# WL_430.net
KiCad netlist of a schematic drawn in Altium Designer
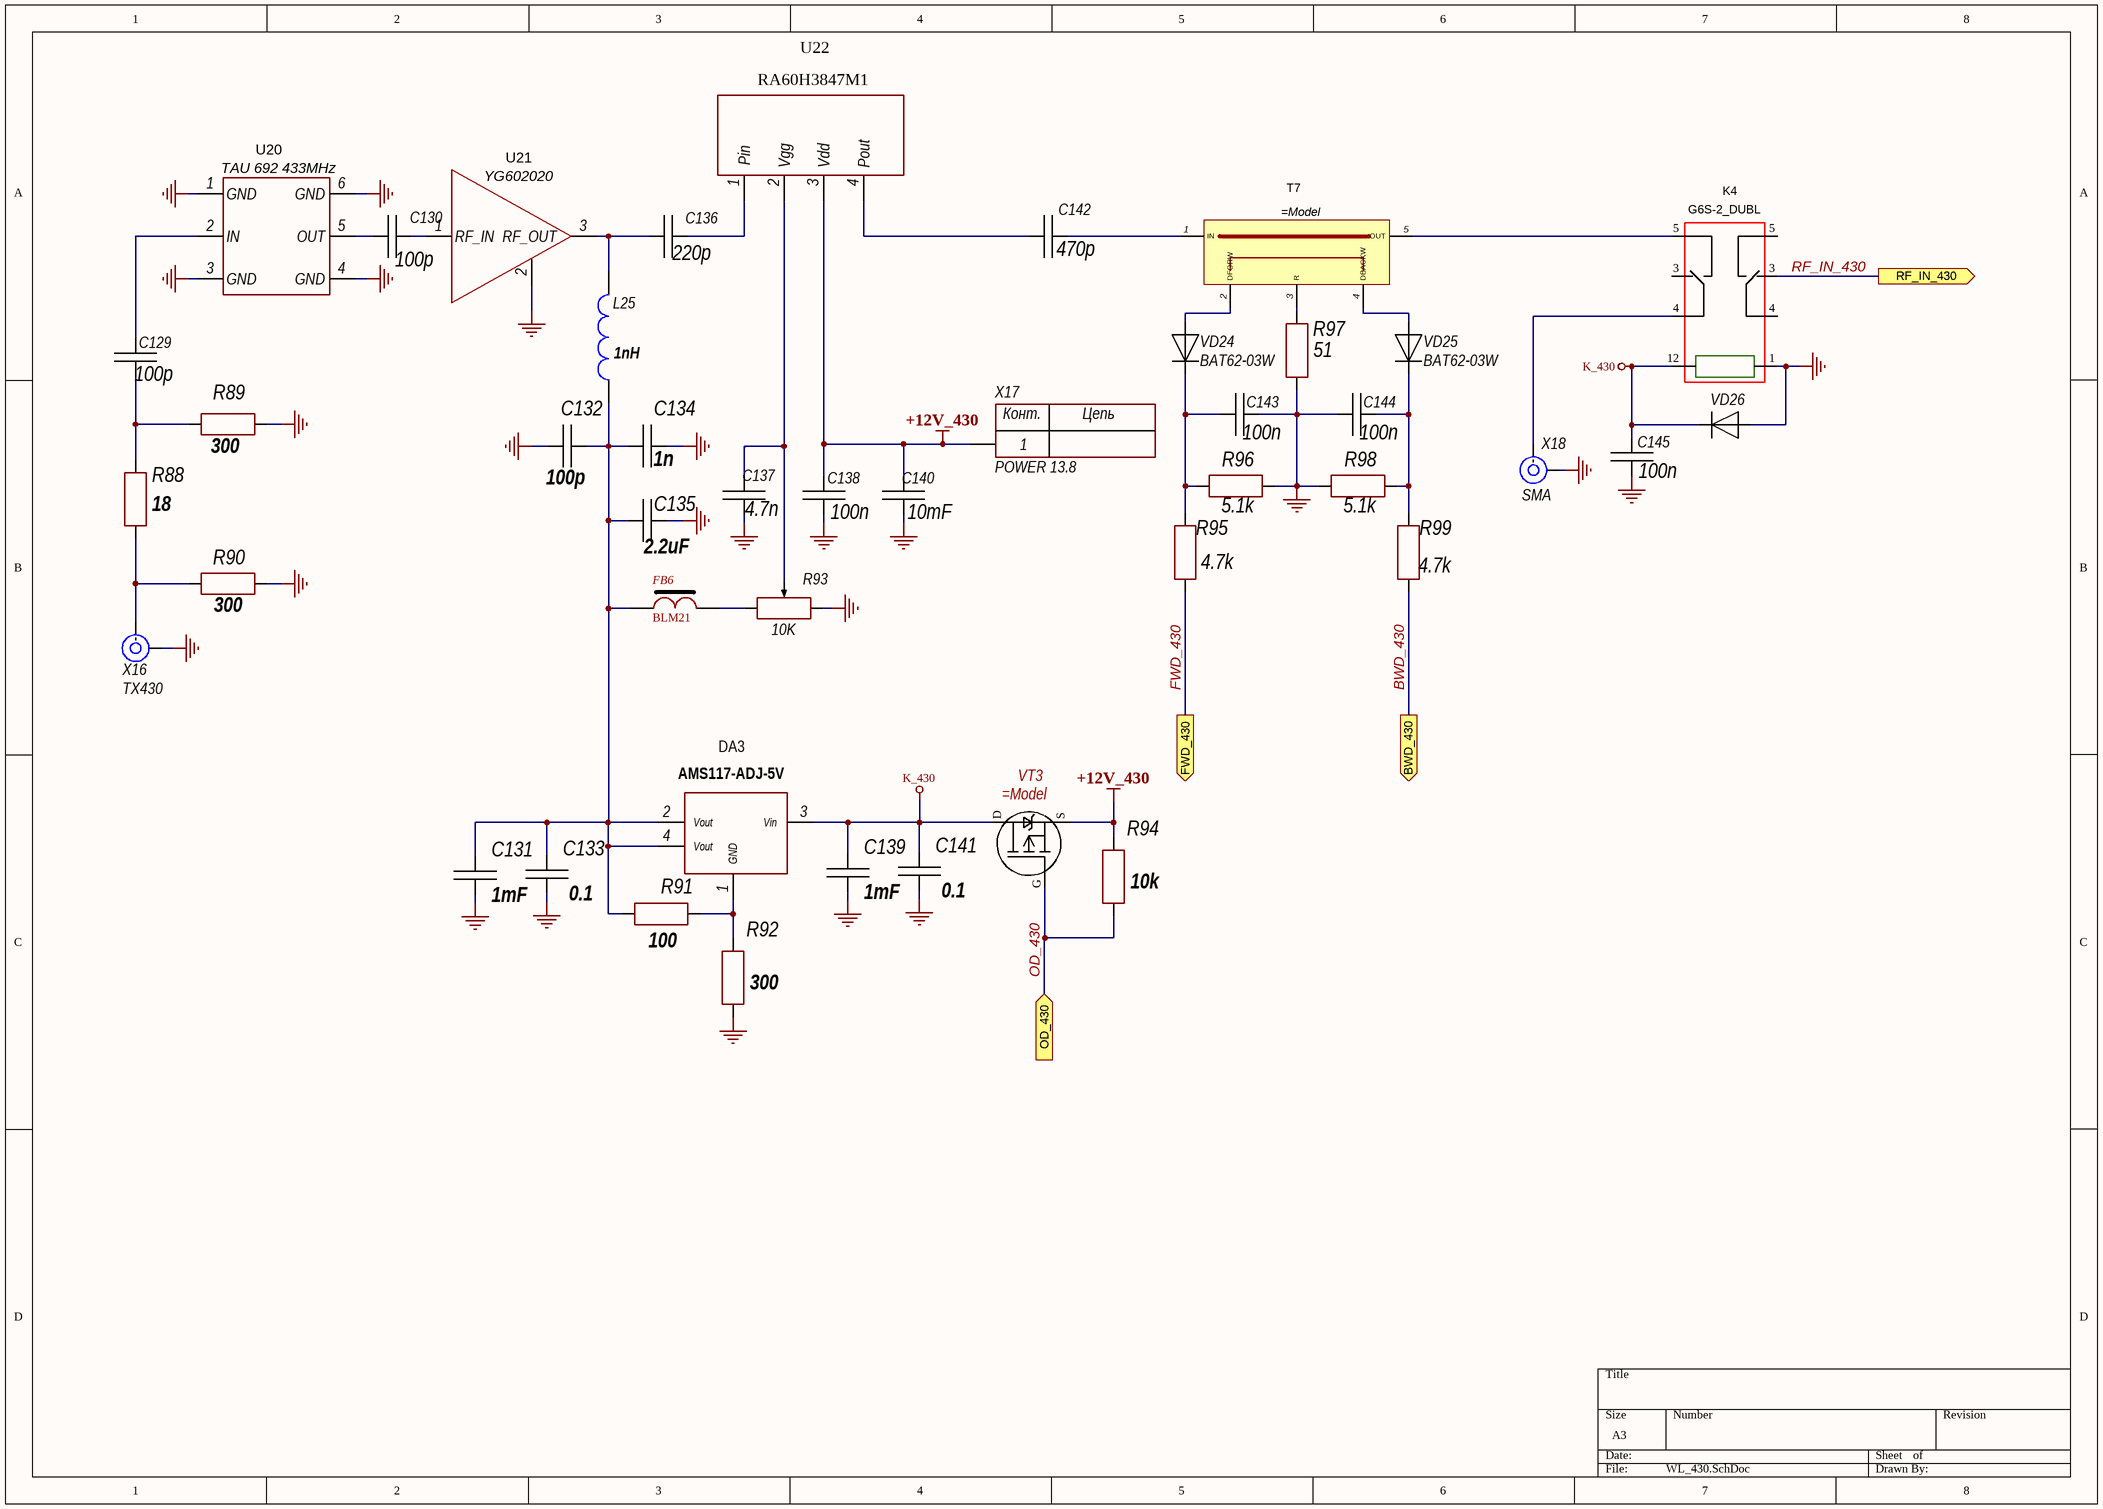
[diagram p0: WL_430.SchDoc]

(export (version "E")
  (design (tool "Eeschema 10.0.6"))
  (components
    (comp (ref "C129")
      (value "100p")
      (footprint "standard:CH0805C")
      (libsource (lib "Discrete") (part "Capacitor"))
    )
    (comp (ref "C130")
      (value "100p")
      (footprint "standard:CH0805C")
      (libsource (lib "Discrete") (part "Capacitor"))
    )
    (comp (ref "C131")
      (value "1mF")
      (footprint "standard:CH0805C")
      (libsource (lib "Discrete") (part "Capacitor"))
    )
    (comp (ref "C132")
      (value "100p")
      (footprint "standard:CH0805C")
      (libsource (lib "Discrete") (part "Capacitor"))
    )
    (comp (ref "C133")
      (value "0.1")
      (footprint "standard:CH0805C")
      (libsource (lib "Discrete") (part "Capacitor"))
    )
    (comp (ref "C134")
      (value "1n")
      (footprint "standard:CH0805C")
      (libsource (lib "Discrete") (part "Capacitor"))
    )
    (comp (ref "C135")
      (value "2.2uF")
      (footprint "standard:CH0805C")
      (libsource (lib "Discrete") (part "Capacitor"))
    )
    (comp (ref "C136")
      (value "220p")
      (footprint "standard:CH0805C")
      (libsource (lib "Discrete") (part "Capacitor"))
    )
    (comp (ref "C137")
      (value "4.7n")
      (footprint "standard:CH0805C")
      (libsource (lib "Discrete") (part "Capacitor"))
    )
    (comp (ref "C138")
      (value "100n")
      (footprint "standard:CH1206C")
      (libsource (lib "Discrete") (part "Capacitor"))
    )
    (comp (ref "C139")
      (value "1mF")
      (footprint "standard:CH0805C")
      (libsource (lib "Discrete") (part "Capacitor"))
    )
    (comp (ref "C140")
      (value "10mF")
      (footprint "standard:CH1206C")
      (libsource (lib "Discrete") (part "Capacitor"))
    )
    (comp (ref "C141")
      (value "0.1")
      (footprint "standard:CH0805C")
      (libsource (lib "Discrete") (part "Capacitor"))
    )
    (comp (ref "C142")
      (value "470p")
      (footprint "standard:CH1210C")
      (libsource (lib "Discrete") (part "Capacitor"))
    )
    (comp (ref "C143")
      (value "100n")
      (footprint "standard:CH0805C")
      (libsource (lib "Discrete") (part "Capacitor"))
    )
    (comp (ref "C144")
      (value "100n")
      (footprint "standard:CH0805C")
      (libsource (lib "Discrete") (part "Capacitor"))
    )
    (comp (ref "C145")
      (value "100n")
      (footprint "standard:CH0805C")
      (libsource (lib "") (part "Capacitor_1"))
    )
    (comp (ref "DA3") (value "AMS117-ADJ-5V") (footprint "SOT223") (libsource (lib "Analog") (part "AMS117")))
    (comp (ref "FB6") (value "BLM21") (footprint "CH0805L") (libsource (lib "Discrete") (part "FB-1")))
    (comp (ref "K4")
      (value "G6S-2_DUBL")
      (footprint "G6S-2_DUBL")
      (libsource (lib "Relay") (part "G6S-2_DUBL"))
    )
    (comp (ref "L25")
      (value "1nH")
      (footprint "katuhka")
      (libsource (lib "Transformers") (part "Inductor ring"))
    )
    (comp (ref "R88") (value "18") (footprint "standard:CH0805R") (libsource (lib "") (part "Resistor_1")))
    (comp (ref "R89") (value "300") (footprint "standard:CH0805R") (libsource (lib "") (part "Resistor_2")))
    (comp (ref "R90") (value "300") (footprint "standard:CH0805R") (libsource (lib "") (part "Resistor_2")))
    (comp (ref "R91") (value "100") (footprint "standard:CH0805R") (libsource (lib "") (part "Resistor_2")))
    (comp (ref "R92")
      (value "300")
      (footprint "standard:CH0805R")
      (libsource (lib "Discrete") (part "Resistor"))
    )
    (comp (ref "R93")
      (value "10K")
      (footprint "custom:RES: 3296W")
      (libsource (lib "Discrete") (part "ADJ resistor"))
    )
    (comp (ref "R94")
      (value "10k")
      (footprint "standard:CH0805R")
      (libsource (lib "Discrete") (part "Resistor"))
    )
    (comp (ref "R95") (value "4.7k") (footprint "standard:CH0805R") (libsource (lib "") (part "Resistor_1")))
    (comp (ref "R96") (value "5.1k") (footprint "standard:CH0805R") (libsource (lib "") (part "Resistor_2")))
    (comp (ref "R97")
      (value "51")
      (footprint "standard:CH1206R")
      (libsource (lib "Discrete") (part "Resistor"))
    )
    (comp (ref "R98") (value "5.1k") (footprint "standard:CH0805R") (libsource (lib "") (part "Resistor_2")))
    (comp (ref "R99") (value "4.7k") (footprint "standard:CH0805R") (libsource (lib "") (part "Resistor_1")))
    (comp (ref "T7") (value "~") (footprint "SWR_D") (libsource (lib "Transformers") (part "VHF_KSV1")))
    (comp (ref "U20")
      (value "TAU 692 433MHz")
      (footprint "TAU692")
      (libsource (lib "Digital") (part "TAU692"))
    )
    (comp (ref "U21")
      (value "YG602020")
      (footprint "SOT89_123")
      (libsource (lib "Digital") (part "YG602020"))
    )
    (comp (ref "U22")
      (value "RA60H3847M1")
      (footprint "RA80H1415M1 - duplicate")
      (libsource (lib "Digital") (part "RA80H1415M1"))
    )
    (comp (ref "VD24") (value "BAT62-03W") (footprint "1N4148") (libsource (lib "Diods") (part "Diod")))
    (comp (ref "VD25") (value "BAT62-03W") (footprint "1N4148") (libsource (lib "Diods") (part "Diod")))
    (comp (ref "VD26") (value "~") (footprint "1N4148") (libsource (lib "Diods") (part "Diod")))
    (comp (ref "VT3") (value "~") (footprint "SOT23_132") (libsource (lib "Transistor") (part "P-KANAL")))
    (comp (ref "X16")
      (value "TX430")
      (footprint "CON: u.Fl")
      (description "RF")
      (libsource (lib "Connectors") (part "SMA"))
    )
    (comp (ref "X17")
      (value "POWER 13.8")
      (footprint "CON: KNIFE_5MM")
      (libsource (lib "Connectors") (part "1-Connector"))
    )
    (comp (ref "X18")
      (value "SMA")
      (footprint "custom:CON: SMA")
      (description "RF")
      (libsource (lib "Connectors") (part "SMA"))
    )
  )
  (nets
    (net (code "1") (name "+12V_430") (class "Default")
      (node (ref "C138") (pin "2") (pinfunction "2_2") (pintype "power_in"))
      (node (ref "C140") (pin "2") (pinfunction "2_2") (pintype "power_in"))
      (node (ref "R94") (pin "2") (pinfunction "2_2") (pintype "passive"))
      (node (ref "U22") (pin "3") (pinfunction "Vdd_3") (pintype "passive"))
      (node (ref "VT3") (pin "2") (pinfunction "Исток_2") (pintype "passive"))
      (node (ref "X17") (pin "1") (pinfunction "1_1") (pintype "passive"))
    )
    (net (code "2") (name "/BWD_430") (class "Default")
      (node (ref "R99") (pin "2") (pinfunction "2_2") (pintype "passive"))
    )
    (net (code "3") (name "/FWD_430") (class "Default")
      (node (ref "R95") (pin "2") (pinfunction "2_2") (pintype "passive"))
    )
    (net (code "4") (name "/OD_430") (class "Default")
      (node (ref "R94") (pin "1") (pinfunction "1_1") (pintype "passive"))
      (node (ref "VT3") (pin "1") (pinfunction "Затвор(Gate)_1") (pintype "passive"))
    )
    (net (code "5") (name "/RF_IN_430") (class "Default")
      (node (ref "K4") (pin "3") (pinfunction "3_3") (pintype "passive"))
    )
    (net (code "6") (name "GND") (class "Default")
      (node (ref "C131") (pin "1") (pinfunction "1_1") (pintype "power_in"))
      (node (ref "C132") (pin "2") (pinfunction "2_2") (pintype "power_in"))
      (node (ref "C133") (pin "1") (pinfunction "1_1") (pintype "power_in"))
      (node (ref "C134") (pin "2") (pinfunction "2_2") (pintype "power_in"))
      (node (ref "C135") (pin "2") (pinfunction "2_2") (pintype "power_in"))
      (node (ref "C137") (pin "1") (pinfunction "1_1") (pintype "power_in"))
      (node (ref "C138") (pin "1") (pinfunction "1_1") (pintype "power_in"))
      (node (ref "C139") (pin "1") (pinfunction "1_1") (pintype "power_in"))
      (node (ref "C140") (pin "1") (pinfunction "1_1") (pintype "power_in"))
      (node (ref "C141") (pin "1") (pinfunction "1_1") (pintype "power_in"))
      (node (ref "C143") (pin "1") (pinfunction "1_1") (pintype "power_in"))
      (node (ref "C144") (pin "2") (pinfunction "2_2") (pintype "power_in"))
      (node (ref "C145") (pin "2") (pinfunction "2_2") (pintype "power_in"))
      (node (ref "K4") (pin "1") (pinfunction "1_1") (pintype "passive"))
      (node (ref "R89") (pin "1") (pinfunction "1_1") (pintype "passive"))
      (node (ref "R90") (pin "1") (pinfunction "1_1") (pintype "passive"))
      (node (ref "R92") (pin "1") (pinfunction "1_1") (pintype "passive"))
      (node (ref "R93") (pin "1") (pinfunction "1_1") (pintype "passive"))
      (node (ref "R96") (pin "1") (pinfunction "1_1") (pintype "passive"))
      (node (ref "R97") (pin "1") (pinfunction "1_1") (pintype "passive"))
      (node (ref "R98") (pin "2") (pinfunction "2_2") (pintype "passive"))
      (node (ref "U20") (pin "1") (pinfunction "GND_1") (pintype "passive"))
      (node (ref "U20") (pin "3") (pinfunction "GND_3") (pintype "passive"))
      (node (ref "U20") (pin "4") (pinfunction "GND_4") (pintype "passive"))
      (node (ref "U20") (pin "6") (pinfunction "GND_6") (pintype "passive"))
      (node (ref "U21") (pin "2") (pinfunction "GND_2") (pintype "passive"))
      (node (ref "VD26") (pin "1") (pinfunction "1_1") (pintype "passive"))
      (node (ref "X16") (pin "2") (pinfunction "IN_2") (pintype "passive"))
      (node (ref "X18") (pin "2") (pinfunction "IN_2") (pintype "passive"))
    )
    (net (code "7") (name "K_430") (class "Default")
      (node (ref "C139") (pin "2") (pinfunction "2_2") (pintype "power_in"))
      (node (ref "C141") (pin "2") (pinfunction "2_2") (pintype "power_in"))
      (node (ref "C145") (pin "1") (pinfunction "1_1") (pintype "power_in"))
      (node (ref "DA3") (pin "3") (pinfunction "Vin_3") (pintype "passive"))
      (node (ref "K4") (pin "12") (pinfunction "12_12") (pintype "passive"))
      (node (ref "VD26") (pin "2") (pinfunction "2_2") (pintype "passive"))
      (node (ref "VT3") (pin "3") (pinfunction "Сток_3") (pintype "passive"))
    )
    (net (code "8") (name "Net-(C129-Pad2)") (class "Default")
      (node (ref "C129") (pin "2") (pinfunction "2_2") (pintype "power_in"))
      (node (ref "R88") (pin "1") (pinfunction "1_1") (pintype "passive"))
      (node (ref "R89") (pin "2") (pinfunction "2_2") (pintype "passive"))
    )
    (net (code "9") (name "Net-(C131-Pad2)") (class "Default")
      (node (ref "C131") (pin "2") (pinfunction "2_2") (pintype "power_in"))
      (node (ref "C132") (pin "1") (pinfunction "1_1") (pintype "power_in"))
      (node (ref "C133") (pin "2") (pinfunction "2_2") (pintype "power_in"))
      (node (ref "C134") (pin "1") (pinfunction "1_1") (pintype "power_in"))
      (node (ref "C135") (pin "1") (pinfunction "1_1") (pintype "power_in"))
      (node (ref "DA3") (pin "2") (pinfunction "Vout_2") (pintype "passive"))
      (node (ref "DA3") (pin "4") (pinfunction "Vout_4") (pintype "passive"))
      (node (ref "FB6") (pin "1") (pinfunction "1_1") (pintype "passive"))
      (node (ref "L25") (pin "2") (pinfunction "2_2") (pintype "passive"))
      (node (ref "R91") (pin "2") (pinfunction "2_2") (pintype "passive"))
    )
    (net (code "10") (name "Net-(C143-Pad2)") (class "Default")
      (node (ref "C143") (pin "2") (pinfunction "2_2") (pintype "power_in"))
      (node (ref "R95") (pin "1") (pinfunction "1_1") (pintype "passive"))
      (node (ref "R96") (pin "2") (pinfunction "2_2") (pintype "passive"))
      (node (ref "VD24") (pin "2") (pinfunction "2_2") (pintype "passive"))
    )
    (net (code "11") (name "Net-(C144-Pad1)") (class "Default")
      (node (ref "C144") (pin "1") (pinfunction "1_1") (pintype "power_in"))
      (node (ref "R98") (pin "1") (pinfunction "1_1") (pintype "passive"))
      (node (ref "R99") (pin "1") (pinfunction "1_1") (pintype "passive"))
      (node (ref "VD25") (pin "2") (pinfunction "2_2") (pintype "passive"))
    )
    (net (code "12") (name "Net-(DA3-GND)") (class "Default")
      (node (ref "DA3") (pin "1") (pinfunction "GND_1") (pintype "passive"))
      (node (ref "R91") (pin "1") (pinfunction "1_1") (pintype "passive"))
      (node (ref "R92") (pin "2") (pinfunction "2_2") (pintype "passive"))
    )
    (net (code "13") (name "Net-(FB6-Pad2)") (class "Default")
      (node (ref "FB6") (pin "2") (pinfunction "2_2") (pintype "passive"))
      (node (ref "R93") (pin "3") (pinfunction "3_3") (pintype "passive"))
    )
    (net (code "14") (name "Net-(K4-Pad4)_1") (class "Default")
      (node (ref "K4") (pin "4") (pinfunction "4_4") (pintype "passive"))
      (node (ref "X18") (pin "1") (pinfunction "IN_1") (pintype "passive"))
    )
    (net (code "15") (name "Net-(R88-Pad2)") (class "Default")
      (node (ref "R88") (pin "2") (pinfunction "2_2") (pintype "passive"))
      (node (ref "R90") (pin "2") (pinfunction "2_2") (pintype "passive"))
      (node (ref "X16") (pin "1") (pinfunction "IN_1") (pintype "passive"))
    )
    (net (code "16") (name "Net-(T7-DBACKW)") (class "Default")
      (node (ref "T7") (pin "4") (pinfunction "DBACKW_4") (pintype "passive"))
      (node (ref "VD25") (pin "1") (pinfunction "1_1") (pintype "passive"))
    )
    (net (code "17") (name "Net-(T7-DFORW)") (class "Default")
      (node (ref "T7") (pin "2") (pinfunction "DFORW_2") (pintype "passive"))
      (node (ref "VD24") (pin "1") (pinfunction "1_1") (pintype "passive"))
    )
    (net (code "18") (name "Net-(T7-IN)") (class "Default")
      (node (ref "C142") (pin "1") (pinfunction "1_1") (pintype "power_in"))
      (node (ref "T7") (pin "1") (pinfunction "IN_1") (pintype "passive"))
    )
    (net (code "19") (name "Net-(T7-OUT)") (class "Default")
      (node (ref "K4") (pin "5") (pinfunction "5_5") (pintype "passive"))
      (node (ref "T7") (pin "5") (pinfunction "OUT_5") (pintype "passive"))
    )
    (net (code "20") (name "Net-(T7-R)") (class "Default")
      (node (ref "R97") (pin "2") (pinfunction "2_2") (pintype "passive"))
      (node (ref "T7") (pin "3") (pinfunction "R_3") (pintype "passive"))
    )
    (net (code "21") (name "Net-(U20-IN)") (class "Default")
      (node (ref "C129") (pin "1") (pinfunction "1_1") (pintype "power_in"))
      (node (ref "U20") (pin "2") (pinfunction "IN_2") (pintype "passive"))
    )
    (net (code "22") (name "Net-(U20-OUT)") (class "Default")
      (node (ref "C130") (pin "2") (pinfunction "2_2") (pintype "power_in"))
      (node (ref "U20") (pin "5") (pinfunction "OUT_5") (pintype "passive"))
    )
    (net (code "23") (name "Net-(U21-RF_IN)") (class "Default")
      (node (ref "C130") (pin "1") (pinfunction "1_1") (pintype "power_in"))
      (node (ref "U21") (pin "1") (pinfunction "RF_IN_1") (pintype "passive"))
    )
    (net (code "24") (name "Net-(U21-RF_OUT)") (class "Default")
      (node (ref "C136") (pin "2") (pinfunction "2_2") (pintype "power_in"))
      (node (ref "L25") (pin "1") (pinfunction "1_1") (pintype "passive"))
      (node (ref "U21") (pin "3") (pinfunction "RF_OUT_3") (pintype "passive"))
    )
    (net (code "25") (name "Net-(U22-Pin)") (class "Default")
      (node (ref "C136") (pin "1") (pinfunction "1_1") (pintype "power_in"))
      (node (ref "U22") (pin "1") (pinfunction "Pin_1") (pintype "passive"))
    )
    (net (code "26") (name "Net-(U22-Pout)") (class "Default")
      (node (ref "C142") (pin "2") (pinfunction "2_2") (pintype "power_in"))
      (node (ref "U22") (pin "4") (pinfunction "Pout_4") (pintype "passive"))
    )
    (net (code "27") (name "Net-(U22-Vgg)") (class "Default")
      (node (ref "C137") (pin "2") (pinfunction "2_2") (pintype "power_in"))
      (node (ref "R93") (pin "2") (pinfunction "2_2") (pintype "passive"))
      (node (ref "U22") (pin "2") (pinfunction "Vgg_2") (pintype "passive"))
    )
    (net (code "28") (name "unconnected-(K4-Pad3)") (class "Default")
      (node (ref "K4") (pin "3") (pinfunction "3_3") (pintype "passive"))
    )
    (net (code "29") (name "unconnected-(K4-Pad4)") (class "Default")
      (node (ref "K4") (pin "4") (pinfunction "4_4") (pintype "passive"))
    )
    (net (code "30") (name "unconnected-(K4-Pad5)") (class "Default")
      (node (ref "K4") (pin "5") (pinfunction "5_5") (pintype "passive"))
    )
  )
)
